# control_board.net
KiCad netlist of a schematic drawn in EAGLE
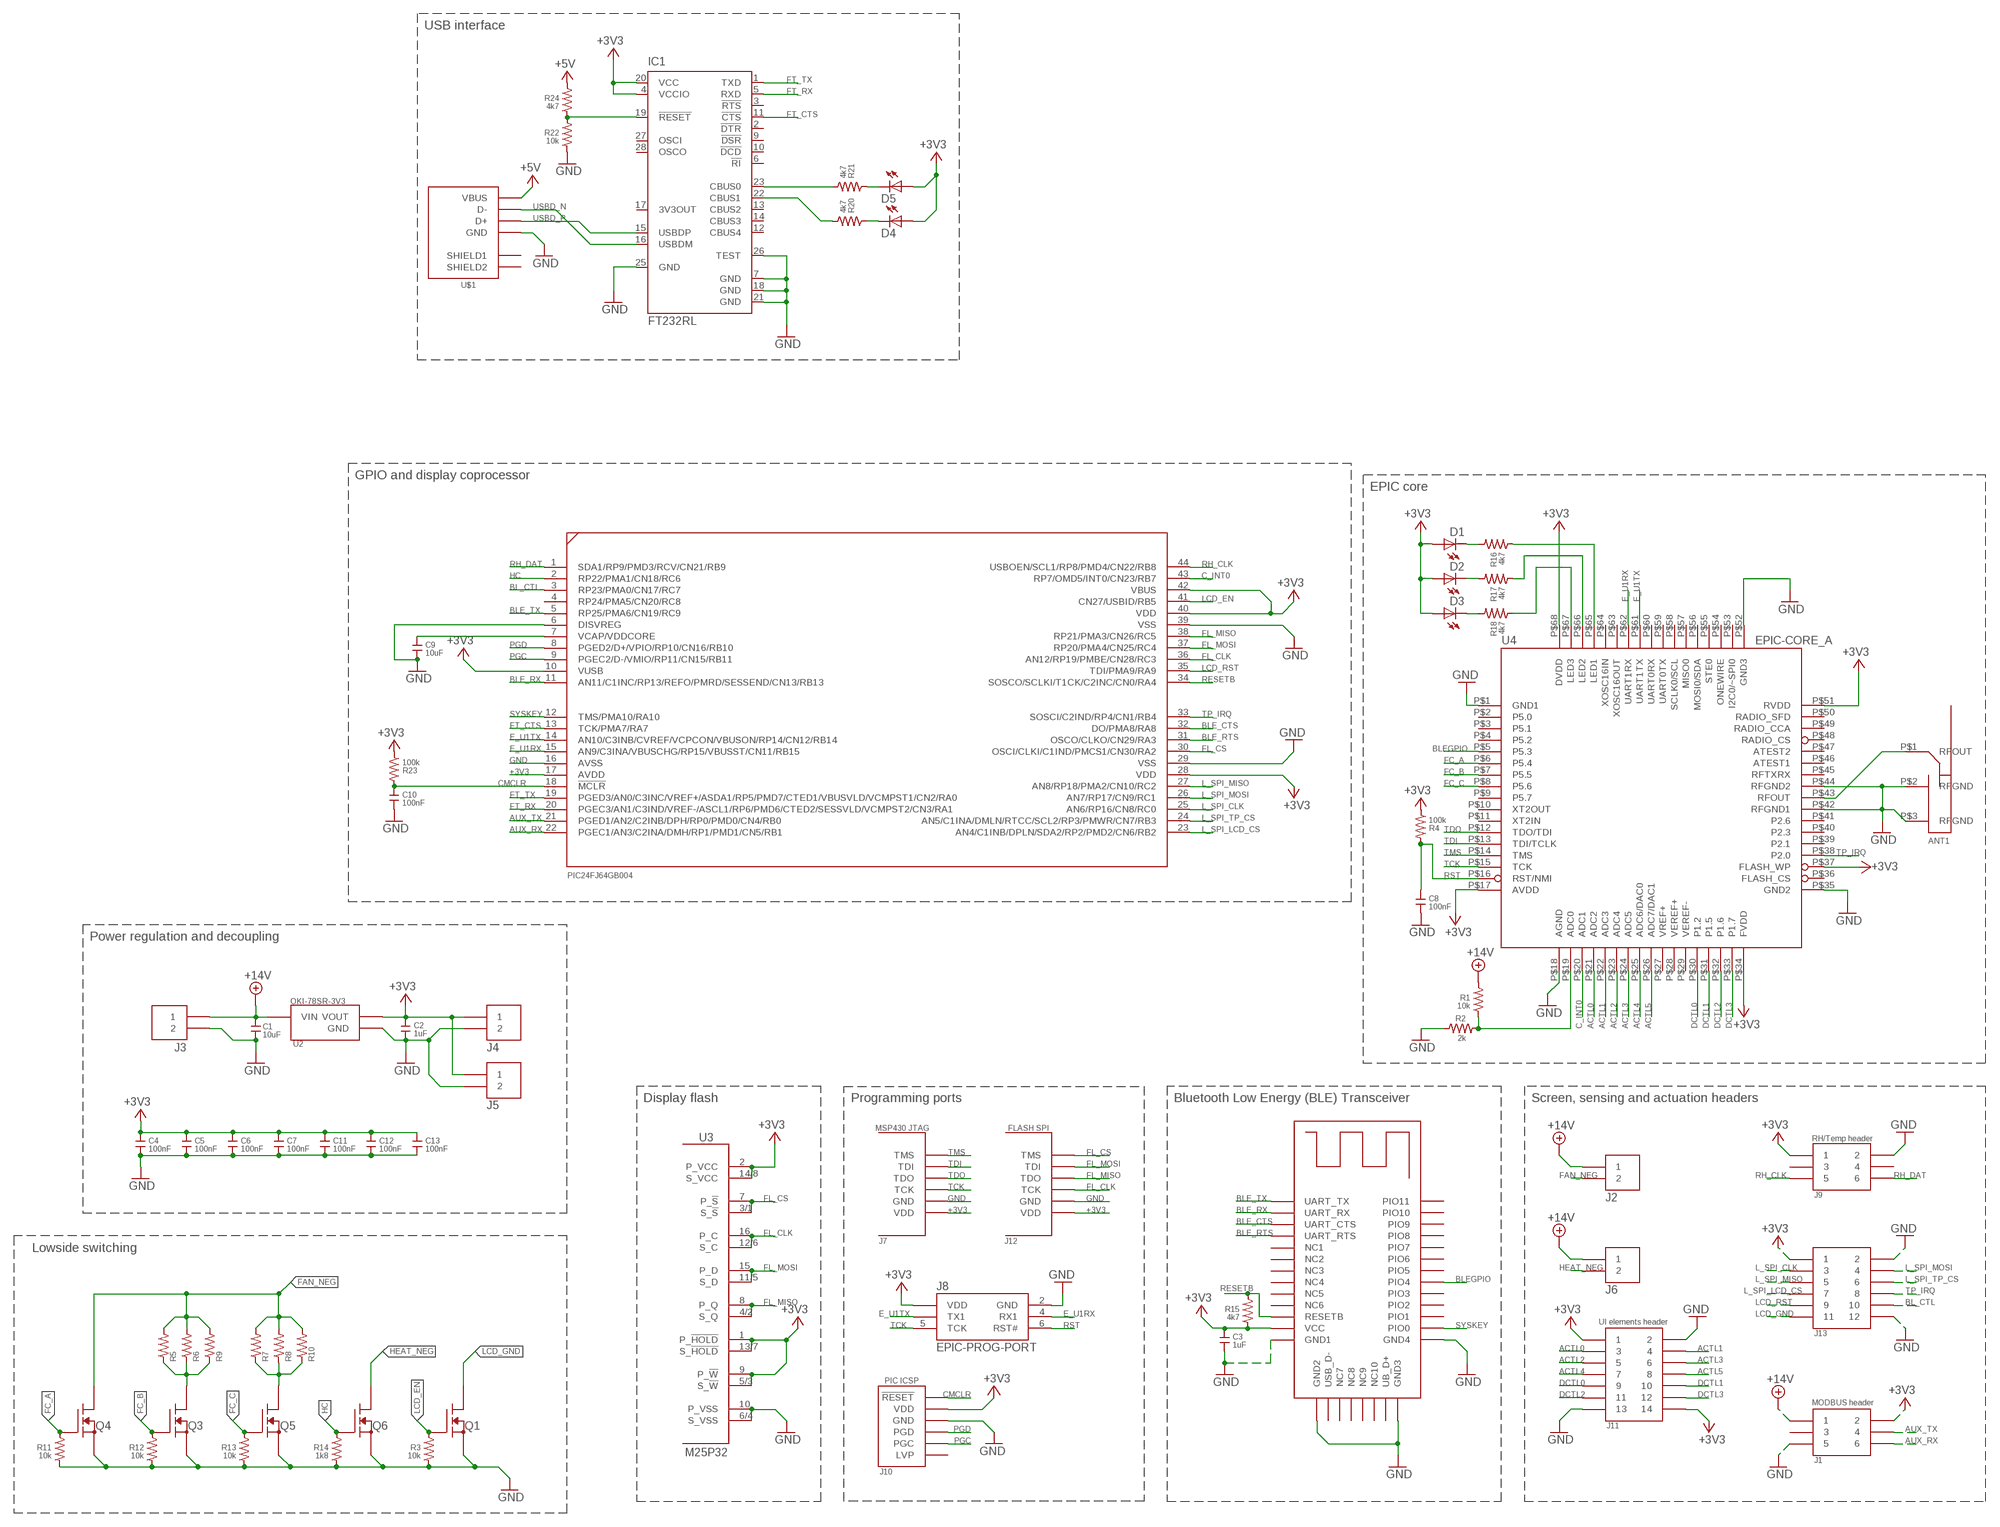
[diagram p0: schematic, sheet 1]

(export (version "E")
  (design (tool "Eeschema 10.0.6"))
  (components
    (comp (ref "ANT1")
      (value "PIFA-2.4GHZ")
      (footprint "eagle-import:PIFA-2.4GHZ")
      (libsource (lib "eagle-import") (part "PIFA-2.4GHZ"))
    )
    (comp (ref "BLE1")
      (value "HM10_BLE")
      (footprint "eagle-import:HM10")
      (libsource (lib "eagle-import") (part "HM10_BLE"))
    )
    (comp (ref "C1")
      (value "10uF")
      (footprint "eagle-import:0805")
      (libsource (lib "eagle-import") (part "0805_CAPACITOR"))
    )
    (comp (ref "C2")
      (value "1uF")
      (footprint "eagle-import:0805")
      (libsource (lib "eagle-import") (part "0805_CAPACITOR"))
    )
    (comp (ref "C3")
      (value "1uF")
      (footprint "eagle-import:0805")
      (libsource (lib "eagle-import") (part "0805_CAPACITOR"))
    )
    (comp (ref "C4")
      (value "100nF")
      (footprint "eagle-import:0805")
      (libsource (lib "eagle-import") (part "0805_CAPACITOR"))
    )
    (comp (ref "C5")
      (value "100nF")
      (footprint "eagle-import:0805")
      (libsource (lib "eagle-import") (part "0805_CAPACITOR"))
    )
    (comp (ref "C6")
      (value "100nF")
      (footprint "eagle-import:0805")
      (libsource (lib "eagle-import") (part "0805_CAPACITOR"))
    )
    (comp (ref "C7")
      (value "100nF")
      (footprint "eagle-import:0805")
      (libsource (lib "eagle-import") (part "0805_CAPACITOR"))
    )
    (comp (ref "C8")
      (value "100nF")
      (footprint "eagle-import:0805")
      (libsource (lib "eagle-import") (part "0805_CAPACITOR"))
    )
    (comp (ref "C9")
      (value "10uF")
      (footprint "eagle-import:0805")
      (libsource (lib "eagle-import") (part "0805_CAPACITOR"))
    )
    (comp (ref "C10")
      (value "100nF")
      (footprint "eagle-import:0805")
      (libsource (lib "eagle-import") (part "0805_CAPACITOR"))
    )
    (comp (ref "C11")
      (value "100nF")
      (footprint "eagle-import:0805")
      (libsource (lib "eagle-import") (part "0805_CAPACITOR"))
    )
    (comp (ref "C12")
      (value "100nF")
      (footprint "eagle-import:0805")
      (libsource (lib "eagle-import") (part "0805_CAPACITOR"))
    )
    (comp (ref "C13")
      (value "100nF")
      (footprint "eagle-import:0805")
      (libsource (lib "eagle-import") (part "0805_CAPACITOR"))
    )
    (comp (ref "D1")
      (value "LED0603")
      (footprint "eagle-import:LED-0603")
      (libsource (lib "eagle-import") (part "LED0603"))
    )
    (comp (ref "D2")
      (value "LED0603")
      (footprint "eagle-import:LED-0603")
      (libsource (lib "eagle-import") (part "LED0603"))
    )
    (comp (ref "D3")
      (value "LED0603")
      (footprint "eagle-import:LED-0603")
      (libsource (lib "eagle-import") (part "LED0603"))
    )
    (comp (ref "D4")
      (value "LED0603")
      (footprint "eagle-import:LED-0603")
      (libsource (lib "eagle-import") (part "LED0603"))
    )
    (comp (ref "D5")
      (value "LED0603")
      (footprint "eagle-import:LED-0603")
      (libsource (lib "eagle-import") (part "LED0603"))
    )
    (comp (ref "IC1")
      (value "FT232RL")
      (footprint "eagle-import:SSOP28")
      (libsource (lib "eagle-import") (part "FT232RL"))
    )
    (comp (ref "J1")
      (value "HD.1-6")
      (footprint "eagle-import:HD.1-6")
      (libsource (lib "eagle-import") (part "HD.1-6"))
    )
    (comp (ref "J2")
      (value "H.1-2")
      (footprint "eagle-import:H.1-2")
      (libsource (lib "eagle-import") (part "H.1-2"))
    )
    (comp (ref "J3")
      (value "H.1-2")
      (footprint "eagle-import:H.1-2")
      (libsource (lib "eagle-import") (part "H.1-2"))
    )
    (comp (ref "J4")
      (value "H.1-2")
      (footprint "eagle-import:H.1-2")
      (libsource (lib "eagle-import") (part "H.1-2"))
    )
    (comp (ref "J5")
      (value "H.1-2")
      (footprint "eagle-import:H.1-2")
      (libsource (lib "eagle-import") (part "H.1-2"))
    )
    (comp (ref "J6")
      (value "H.1-2")
      (footprint "eagle-import:H.1-2")
      (libsource (lib "eagle-import") (part "H.1-2"))
    )
    (comp (ref "J7")
      (value "JTAG")
      (footprint "eagle-import:JTAG")
      (libsource (lib "eagle-import") (part "JTAG"))
    )
    (comp (ref "J8")
      (value "EPIC-PROG-PORT")
      (footprint "eagle-import:HEADER2X3X2MM")
      (libsource (lib "eagle-import") (part "EPIC-PROG-PORT"))
    )
    (comp (ref "J9")
      (value "HD.1-6")
      (footprint "eagle-import:HD.1-6")
      (libsource (lib "eagle-import") (part "HD.1-6"))
    )
    (comp (ref "J10")
      (value "ICSP_HDR")
      (footprint "eagle-import:H.1-6")
      (libsource (lib "eagle-import") (part "ICSP_HDR"))
    )
    (comp (ref "J11")
      (value "HD.1-14")
      (footprint "eagle-import:HD.1-16")
      (libsource (lib "eagle-import") (part "HD.1-14"))
    )
    (comp (ref "J12")
      (value "JTAG")
      (footprint "eagle-import:JTAG")
      (libsource (lib "eagle-import") (part "JTAG"))
    )
    (comp (ref "J13")
      (value "HD.1-12")
      (footprint "eagle-import:HD.1-12")
      (libsource (lib "eagle-import") (part "HD.1-12"))
    )
    (comp (ref "Q1")
      (value "NFET_DPAK")
      (footprint "eagle-import:DPAK")
      (libsource (lib "eagle-import") (part "NFET_DPAK"))
    )
    (comp (ref "Q3")
      (value "NFET_DPAK")
      (footprint "eagle-import:DPAK")
      (libsource (lib "eagle-import") (part "NFET_DPAK"))
    )
    (comp (ref "Q4")
      (value "NFET_DPAK")
      (footprint "eagle-import:DPAK")
      (libsource (lib "eagle-import") (part "NFET_DPAK"))
    )
    (comp (ref "Q5")
      (value "NFET_DPAK")
      (footprint "eagle-import:DPAK")
      (libsource (lib "eagle-import") (part "NFET_DPAK"))
    )
    (comp (ref "Q6")
      (value "NFET_DPAK")
      (footprint "eagle-import:DPAK")
      (libsource (lib "eagle-import") (part "NFET_DPAK"))
    )
    (comp (ref "R1")
      (value "10k")
      (footprint "eagle-import:0805")
      (libsource (lib "eagle-import") (part "0805_RESISTOR"))
    )
    (comp (ref "R2")
      (value "2k")
      (footprint "eagle-import:0805")
      (libsource (lib "eagle-import") (part "0805_RESISTOR"))
    )
    (comp (ref "R3")
      (value "10k")
      (footprint "eagle-import:0805")
      (libsource (lib "eagle-import") (part "0805_RESISTOR"))
    )
    (comp (ref "R4")
      (value "100k")
      (footprint "eagle-import:0805")
      (libsource (lib "eagle-import") (part "0805_RESISTOR"))
    )
    (comp (ref "R5")
      (value "1206_RESISTOR")
      (footprint "eagle-import:1206")
      (libsource (lib "eagle-import") (part "1206_RESISTOR"))
    )
    (comp (ref "R6")
      (value "1206_RESISTOR")
      (footprint "eagle-import:1206")
      (libsource (lib "eagle-import") (part "1206_RESISTOR"))
    )
    (comp (ref "R7")
      (value "1206_RESISTOR")
      (footprint "eagle-import:1206")
      (libsource (lib "eagle-import") (part "1206_RESISTOR"))
    )
    (comp (ref "R8")
      (value "1206_RESISTOR")
      (footprint "eagle-import:1206")
      (libsource (lib "eagle-import") (part "1206_RESISTOR"))
    )
    (comp (ref "R9")
      (value "1206_RESISTOR")
      (footprint "eagle-import:1206")
      (libsource (lib "eagle-import") (part "1206_RESISTOR"))
    )
    (comp (ref "R10")
      (value "1206_RESISTOR")
      (footprint "eagle-import:1206")
      (libsource (lib "eagle-import") (part "1206_RESISTOR"))
    )
    (comp (ref "R11")
      (value "10k")
      (footprint "eagle-import:0805")
      (libsource (lib "eagle-import") (part "0805_RESISTOR"))
    )
    (comp (ref "R12")
      (value "10k")
      (footprint "eagle-import:0805")
      (libsource (lib "eagle-import") (part "0805_RESISTOR"))
    )
    (comp (ref "R13")
      (value "10k")
      (footprint "eagle-import:0805")
      (libsource (lib "eagle-import") (part "0805_RESISTOR"))
    )
    (comp (ref "R14")
      (value "1k8")
      (footprint "eagle-import:0805")
      (libsource (lib "eagle-import") (part "0805_RESISTOR"))
    )
    (comp (ref "R15")
      (value "4k7")
      (footprint "eagle-import:0805")
      (libsource (lib "eagle-import") (part "0805_RESISTOR"))
    )
    (comp (ref "R16")
      (value "4k7")
      (footprint "eagle-import:0805")
      (libsource (lib "eagle-import") (part "0805_RESISTOR"))
    )
    (comp (ref "R17")
      (value "4k7")
      (footprint "eagle-import:0805")
      (libsource (lib "eagle-import") (part "0805_RESISTOR"))
    )
    (comp (ref "R18")
      (value "4k7")
      (footprint "eagle-import:0805")
      (libsource (lib "eagle-import") (part "0805_RESISTOR"))
    )
    (comp (ref "R20")
      (value "4k7")
      (footprint "eagle-import:0805")
      (libsource (lib "eagle-import") (part "0805_RESISTOR"))
    )
    (comp (ref "R21")
      (value "4k7")
      (footprint "eagle-import:0805")
      (libsource (lib "eagle-import") (part "0805_RESISTOR"))
    )
    (comp (ref "R22")
      (value "10k")
      (footprint "eagle-import:0805")
      (libsource (lib "eagle-import") (part "0805_RESISTOR"))
    )
    (comp (ref "R23")
      (value "100k")
      (footprint "eagle-import:0805")
      (libsource (lib "eagle-import") (part "0805_RESISTOR"))
    )
    (comp (ref "R24")
      (value "4k7")
      (footprint "eagle-import:0805")
      (libsource (lib "eagle-import") (part "0805_RESISTOR"))
    )
    (comp (ref "U$1")
      (value "USB_B")
      (footprint "eagle-import:USB_MOLEX_7041")
      (libsource (lib "eagle-import") (part "USB_B"))
    )
    (comp (ref "U1")
      (value "PIC24FJ32GB004")
      (footprint "eagle-import:TQFP44")
      (libsource (lib "eagle-import") (part "PIC24FJ32GB004"))
    )
    (comp (ref "U2")
      (value "OKI-78SR_3V3_SMPS")
      (footprint "eagle-import:SMPS_MODULE")
      (libsource (lib "eagle-import") (part "OKI-78SR_3V3_SMPS"))
    )
    (comp (ref "U3")
      (value "NUMONYX_FLASH")
      (footprint "eagle-import:NUMONYX_FLASH")
      (libsource (lib "eagle-import") (part "NUMONYX_FLASH"))
    )
    (comp (ref "U4")
      (value "EPIC-CORE_A")
      (footprint "eagle-import:EPIC-LCC68")
      (libsource (lib "eagle-import") (part "EPIC-CORE_A"))
    )
  )
  (nets
    (net (code "1") (name "+3V3") (class "Default")
      (node (ref "BLE1") (pin "P$12") (pinfunction "VCC_P$12") (pintype "power_in"))
      (node (ref "C11") (pin "2") (pinfunction "P$2_2") (pintype "passive"))
      (node (ref "C12") (pin "2") (pinfunction "P$2_2") (pintype "passive"))
      (node (ref "C13") (pin "2") (pinfunction "P$2_2") (pintype "passive"))
      (node (ref "C2") (pin "2") (pinfunction "P$2_2") (pintype "passive"))
      (node (ref "C3") (pin "2") (pinfunction "P$2_2") (pintype "passive"))
      (node (ref "C4") (pin "2") (pinfunction "P$2_2") (pintype "passive"))
      (node (ref "C5") (pin "2") (pinfunction "P$2_2") (pintype "passive"))
      (node (ref "C6") (pin "2") (pinfunction "P$2_2") (pintype "passive"))
      (node (ref "C7") (pin "2") (pinfunction "P$2_2") (pintype "passive"))
      (node (ref "D1") (pin "A") (pinfunction "A_A") (pintype "passive"))
      (node (ref "D2") (pin "A") (pinfunction "A_A") (pintype "passive"))
      (node (ref "D3") (pin "A") (pinfunction "A_A") (pintype "passive"))
      (node (ref "D4") (pin "A") (pinfunction "A_A") (pintype "passive"))
      (node (ref "D5") (pin "A") (pinfunction "A_A") (pintype "passive"))
      (node (ref "IC1") (pin "20") (pinfunction "VCC_20") (pintype "power_in"))
      (node (ref "IC1") (pin "4") (pinfunction "VCCIO_4") (pintype "power_in"))
      (node (ref "J1") (pin "P2") (pinfunction "2_P2") (pintype "bidirectional"))
      (node (ref "J10") (pin "P2") (pinfunction "VDD_P2") (pintype "bidirectional"))
      (node (ref "J11") (pin "P1") (pinfunction "1_P1") (pintype "bidirectional"))
      (node (ref "J11") (pin "P14") (pinfunction "14_P14") (pintype "bidirectional"))
      (node (ref "J12") (pin "VDD") (pinfunction "VDD_VDD") (pintype "bidirectional"))
      (node (ref "J13") (pin "P1") (pinfunction "1_P1") (pintype "bidirectional"))
      (node (ref "J4") (pin "P1") (pinfunction "1_P1") (pintype "bidirectional"))
      (node (ref "J5") (pin "P1") (pinfunction "1_P1") (pintype "bidirectional"))
      (node (ref "J7") (pin "VDD") (pinfunction "VDD_VDD") (pintype "bidirectional"))
      (node (ref "J8") (pin "1") (pinfunction "VDD_1") (pintype "bidirectional"))
      (node (ref "J9") (pin "P1") (pinfunction "1_P1") (pintype "bidirectional"))
      (node (ref "R15") (pin "1") (pinfunction "P$1_1") (pintype "passive"))
      (node (ref "R23") (pin "1") (pinfunction "P$1_1") (pintype "passive"))
      (node (ref "R4") (pin "1") (pinfunction "P$1_1") (pintype "passive"))
      (node (ref "U1") (pin "10") (pinfunction "VUSB_10") (pintype "bidirectional"))
      (node (ref "U1") (pin "17") (pinfunction "AVDD_17") (pintype "bidirectional"))
      (node (ref "U1") (pin "28") (pinfunction "VDD_28") (pintype "bidirectional"))
      (node (ref "U1") (pin "40") (pinfunction "VDD_40") (pintype "bidirectional"))
      (node (ref "U1") (pin "42") (pinfunction "VBUS_42") (pintype "bidirectional"))
      (node (ref "U2") (pin "VOUT") (pinfunction "VOUT_VOUT") (pintype "power_in"))
      (node (ref "U3") (pin "1") (pinfunction "P_~{HOLD}_1") (pintype "bidirectional"))
      (node (ref "U3") (pin "13/7") (pinfunction "S_~{HOLD}_13/7") (pintype "bidirectional"))
      (node (ref "U3") (pin "14/8") (pinfunction "S_VCC_14/8") (pintype "power_in"))
      (node (ref "U3") (pin "2") (pinfunction "P_VCC_2") (pintype "power_in"))
      (node (ref "U3") (pin "5/3") (pinfunction "S_~{W}_5/3") (pintype "bidirectional"))
      (node (ref "U3") (pin "9") (pinfunction "P_~{W}_9") (pintype "bidirectional"))
      (node (ref "U4") (pin "P$17") (pinfunction "AVDD_P$17") (pintype "bidirectional"))
      (node (ref "U4") (pin "P$34") (pinfunction "FVDD_P$34") (pintype "bidirectional"))
      (node (ref "U4") (pin "P$37") (pinfunction "FLASH_WP_P$37") (pintype "bidirectional"))
      (node (ref "U4") (pin "P$51") (pinfunction "RVDD_P$51") (pintype "bidirectional"))
      (node (ref "U4") (pin "P$68") (pinfunction "DVDD_P$68") (pintype "bidirectional"))
    )
    (net (code "2") (name "+5V") (class "Default")
      (node (ref "R24") (pin "2") (pinfunction "P$2_2") (pintype "passive"))
      (node (ref "U$1") (pin "1_VBUS") (pinfunction "VBUS_1_VBUS") (pintype "bidirectional"))
    )
    (net (code "3") (name "+14V") (class "Default")
      (node (ref "C1") (pin "2") (pinfunction "P$2_2") (pintype "passive"))
      (node (ref "J1") (pin "P1") (pinfunction "1_P1") (pintype "bidirectional"))
      (node (ref "J2") (pin "P1") (pinfunction "1_P1") (pintype "bidirectional"))
      (node (ref "J3") (pin "P1") (pinfunction "1_P1") (pintype "bidirectional"))
      (node (ref "J6") (pin "P1") (pinfunction "1_P1") (pintype "bidirectional"))
      (node (ref "R1") (pin "2") (pinfunction "P$2_2") (pintype "passive"))
      (node (ref "U2") (pin "VIN") (pinfunction "VIN_VIN") (pintype "power_in"))
    )
    (net (code "4") (name "/ACTL0") (class "Default")
      (node (ref "J11") (pin "P3") (pinfunction "3_P3") (pintype "bidirectional"))
      (node (ref "U4") (pin "P$21") (pinfunction "ADC2_P$21") (pintype "bidirectional"))
    )
    (net (code "5") (name "/ACTL1") (class "Default")
      (node (ref "J11") (pin "P4") (pinfunction "4_P4") (pintype "bidirectional"))
      (node (ref "U4") (pin "P$22") (pinfunction "ADC3_P$22") (pintype "bidirectional"))
    )
    (net (code "6") (name "/ACTL2") (class "Default")
      (node (ref "J11") (pin "P5") (pinfunction "5_P5") (pintype "bidirectional"))
      (node (ref "U4") (pin "P$23") (pinfunction "ADC4_P$23") (pintype "bidirectional"))
    )
    (net (code "7") (name "/ACTL3") (class "Default")
      (node (ref "J11") (pin "P6") (pinfunction "6_P6") (pintype "bidirectional"))
      (node (ref "U4") (pin "P$24") (pinfunction "ADC5_P$24") (pintype "bidirectional"))
    )
    (net (code "8") (name "/ACTL4") (class "Default")
      (node (ref "J11") (pin "P7") (pinfunction "7_P7") (pintype "bidirectional"))
      (node (ref "U4") (pin "P$25") (pinfunction "ADC6/DAC0_P$25") (pintype "bidirectional"))
    )
    (net (code "9") (name "/ACTL5") (class "Default")
      (node (ref "J11") (pin "P8") (pinfunction "8_P8") (pintype "bidirectional"))
      (node (ref "U4") (pin "P$26") (pinfunction "ADC7/DAC1_P$26") (pintype "bidirectional"))
    )
    (net (code "10") (name "/AUX_RX") (class "Default")
      (node (ref "J1") (pin "P6") (pinfunction "6_P6") (pintype "bidirectional"))
      (node (ref "U1") (pin "22") (pinfunction "PGEC1/AN3/C2INA/DMH/RP1/PMD1/CN5/RB1_22") (pintype "bidirectional"))
    )
    (net (code "11") (name "/AUX_TX") (class "Default")
      (node (ref "J1") (pin "P4") (pinfunction "4_P4") (pintype "bidirectional"))
      (node (ref "U1") (pin "21") (pinfunction "PGED1/AN2/C2INB/DPH/RP0/PMD0/CN4/RB0_21") (pintype "bidirectional"))
    )
    (net (code "12") (name "/BLEGPIO") (class "Default")
      (node (ref "BLE1") (pin "P$27") (pinfunction "PIO4_P$27") (pintype "bidirectional"))
      (node (ref "U4") (pin "P$5") (pinfunction "P5.3_P$5") (pintype "bidirectional"))
    )
    (net (code "13") (name "/BLE_CTS") (class "Default")
      (node (ref "BLE1") (pin "P$3") (pinfunction "UART_CTS_P$3") (pintype "bidirectional"))
      (node (ref "U1") (pin "32") (pinfunction "DO/PMA8/RA8_32") (pintype "bidirectional"))
    )
    (net (code "14") (name "/BLE_RTS") (class "Default")
      (node (ref "BLE1") (pin "P$4") (pinfunction "UART_RTS_P$4") (pintype "bidirectional"))
      (node (ref "U1") (pin "31") (pinfunction "OSCO/CLKO/CN29/RA3_31") (pintype "bidirectional"))
    )
    (net (code "15") (name "/BLE_RX") (class "Default")
      (node (ref "BLE1") (pin "P$2") (pinfunction "UART_RX_P$2") (pintype "bidirectional"))
      (node (ref "U1") (pin "11") (pinfunction "AN11/C1INC/RP13/REFO/PMRD/SESSEND/CN13/RB13_11") (pintype "bidirectional"))
    )
    (net (code "16") (name "/BLE_TX") (class "Default")
      (node (ref "BLE1") (pin "P$1") (pinfunction "UART_TX_P$1") (pintype "bidirectional"))
      (node (ref "U1") (pin "5") (pinfunction "RP25/PMA6/CN19/RC9_5") (pintype "bidirectional"))
    )
    (net (code "17") (name "/BL_CTL") (class "Default")
      (node (ref "J13") (pin "P10") (pinfunction "10_P10") (pintype "bidirectional"))
      (node (ref "U1") (pin "3") (pinfunction "RP23/PMA0/CN17/RC7_3") (pintype "bidirectional"))
    )
    (net (code "18") (name "/CMCLR") (class "Default")
      (node (ref "C10") (pin "2") (pinfunction "P$2_2") (pintype "passive"))
      (node (ref "J10") (pin "P1") (pinfunction "~{RESET}_P1") (pintype "bidirectional"))
      (node (ref "R23") (pin "2") (pinfunction "P$2_2") (pintype "passive"))
      (node (ref "U1") (pin "18") (pinfunction "~{MCLR}_18") (pintype "bidirectional"))
    )
    (net (code "19") (name "/C_INT0") (class "Default")
      (node (ref "U1") (pin "43") (pinfunction "RP7/OMD5/INT0/CN23/RB7_43") (pintype "bidirectional"))
      (node (ref "U4") (pin "P$20") (pinfunction "ADC1_P$20") (pintype "bidirectional"))
    )
    (net (code "20") (name "/DCTL0") (class "Default")
      (node (ref "J11") (pin "P9") (pinfunction "9_P9") (pintype "bidirectional"))
      (node (ref "U4") (pin "P$30") (pinfunction "P1.2_P$30") (pintype "bidirectional"))
    )
    (net (code "21") (name "/DCTL1") (class "Default")
      (node (ref "J11") (pin "P10") (pinfunction "10_P10") (pintype "bidirectional"))
      (node (ref "U4") (pin "P$31") (pinfunction "P1.5_P$31") (pintype "bidirectional"))
    )
    (net (code "22") (name "/DCTL2") (class "Default")
      (node (ref "J11") (pin "P11") (pinfunction "11_P11") (pintype "bidirectional"))
      (node (ref "U4") (pin "P$32") (pinfunction "P1.6_P$32") (pintype "bidirectional"))
    )
    (net (code "23") (name "/DCTL3") (class "Default")
      (node (ref "J11") (pin "P12") (pinfunction "12_P12") (pintype "bidirectional"))
      (node (ref "U4") (pin "P$33") (pinfunction "P1.7_P$33") (pintype "bidirectional"))
    )
    (net (code "24") (name "/E_U1RX") (class "Default")
      (node (ref "J8") (pin "4") (pinfunction "RX1_4") (pintype "bidirectional"))
      (node (ref "U1") (pin "15") (pinfunction "AN9/C3INA/VBUSCHG/RP15/VBUSST/CN11/RB15_15") (pintype "bidirectional"))
      (node (ref "U4") (pin "P$62") (pinfunction "UART1RX_P$62") (pintype "bidirectional"))
    )
    (net (code "25") (name "/E_U1TX") (class "Default")
      (node (ref "J8") (pin "3") (pinfunction "TX1_3") (pintype "bidirectional"))
      (node (ref "U1") (pin "14") (pinfunction "AN10/C3INB/CVREF/VCPCON/VBUSON/RP14/CN12/RB14_14") (pintype "bidirectional"))
      (node (ref "U4") (pin "P$61") (pinfunction "UART1TX_P$61") (pintype "bidirectional"))
    )
    (net (code "26") (name "/FL_CLK") (class "Default")
      (node (ref "J12") (pin "TCK") (pinfunction "TCK_TCK") (pintype "bidirectional"))
      (node (ref "U1") (pin "36") (pinfunction "AN12/RP19/PMBE/CN28/RC3_36") (pintype "bidirectional"))
      (node (ref "U3") (pin "12/6") (pinfunction "S_C_12/6") (pintype "bidirectional"))
      (node (ref "U3") (pin "16") (pinfunction "P_C_16") (pintype "bidirectional"))
    )
    (net (code "27") (name "/FL_CS") (class "Default")
      (node (ref "J12") (pin "TMS") (pinfunction "TMS_TMS") (pintype "bidirectional"))
      (node (ref "U1") (pin "30") (pinfunction "OSCI/CLKI/C1IND/PMCS1/CN30/RA2_30") (pintype "bidirectional"))
      (node (ref "U3") (pin "3/1") (pinfunction "S_~{S}_3/1") (pintype "bidirectional"))
      (node (ref "U3") (pin "7") (pinfunction "P_~{S}_7") (pintype "bidirectional"))
    )
    (net (code "28") (name "/FL_MISO") (class "Default")
      (node (ref "J12") (pin "TDO") (pinfunction "TDO_TDO") (pintype "bidirectional"))
      (node (ref "U1") (pin "38") (pinfunction "RP21/PMA3/CN26/RC5_38") (pintype "bidirectional"))
      (node (ref "U3") (pin "4/2") (pinfunction "S_Q_4/2") (pintype "bidirectional"))
      (node (ref "U3") (pin "8") (pinfunction "P_Q_8") (pintype "bidirectional"))
    )
    (net (code "29") (name "/FL_MOSI") (class "Default")
      (node (ref "J12") (pin "TDI") (pinfunction "TDI_TDI") (pintype "bidirectional"))
      (node (ref "U1") (pin "37") (pinfunction "RP20/PMA4/CN25/RC4_37") (pintype "bidirectional"))
      (node (ref "U3") (pin "11/5") (pinfunction "S_D_11/5") (pintype "bidirectional"))
      (node (ref "U3") (pin "15") (pinfunction "P_D_15") (pintype "bidirectional"))
    )
    (net (code "30") (name "/FT_CTS") (class "Default")
      (node (ref "IC1") (pin "11") (pinfunction "~{CTS}_11") (pintype "input"))
      (node (ref "U1") (pin "13") (pinfunction "TCK/PMA7/RA7_13") (pintype "bidirectional"))
    )
    (net (code "31") (name "/FT_RX") (class "Default")
      (node (ref "IC1") (pin "5") (pinfunction "RXD_5") (pintype "input"))
      (node (ref "U1") (pin "20") (pinfunction "PGEC3/AN1/C3IND/VREF-/ASCL1/RP6/PMD6/CTED2/SESSVLD/VCMPST2/CN3/RA1_20") (pintype "bidirectional"))
    )
    (net (code "32") (name "/FT_TX") (class "Default")
      (node (ref "IC1") (pin "1") (pinfunction "TXD_1") (pintype "output"))
      (node (ref "U1") (pin "19") (pinfunction "PGED3/AN0/C3INC/VREF+/ASDA1/RP5/PMD7/CTED1/VBUSVLD/VCMPST1/CN2/RA0_19") (pintype "bidirectional"))
    )
    (net (code "33") (name "/LCD_RST") (class "Default")
      (node (ref "J13") (pin "P9") (pinfunction "9_P9") (pintype "bidirectional"))
      (node (ref "U1") (pin "35") (pinfunction "TDI/PMA9/RA9_35") (pintype "bidirectional"))
    )
    (net (code "34") (name "/L_SPI_CLK") (class "Default")
      (node (ref "J13") (pin "P3") (pinfunction "3_P3") (pintype "bidirectional"))
      (node (ref "U1") (pin "25") (pinfunction "AN6/RP16/CN8/RC0_25") (pintype "bidirectional"))
    )
    (net (code "35") (name "/L_SPI_LCD_CS") (class "Default")
      (node (ref "J13") (pin "P7") (pinfunction "7_P7") (pintype "bidirectional"))
      (node (ref "U1") (pin "23") (pinfunction "AN4/C1INB/DPLN/SDA2/RP2/PMD2/CN6/RB2_23") (pintype "bidirectional"))
    )
    (net (code "36") (name "/L_SPI_MISO") (class "Default")
      (node (ref "J13") (pin "P5") (pinfunction "5_P5") (pintype "bidirectional"))
      (node (ref "U1") (pin "27") (pinfunction "AN8/RP18/PMA2/CN10/RC2_27") (pintype "bidirectional"))
    )
    (net (code "37") (name "/L_SPI_MOSI") (class "Default")
      (node (ref "J13") (pin "P4") (pinfunction "4_P4") (pintype "bidirectional"))
      (node (ref "U1") (pin "26") (pinfunction "AN7/RP17/CN9/RC1_26") (pintype "bidirectional"))
    )
    (net (code "38") (name "/L_SPI_TP_CS") (class "Default")
      (node (ref "J13") (pin "P6") (pinfunction "6_P6") (pintype "bidirectional"))
      (node (ref "U1") (pin "24") (pinfunction "AN5/C1INA/DMLN/RTCC/SCL2/RP3/PMWR/CN7/RB3_24") (pintype "bidirectional"))
    )
    (net (code "39") (name "/PGC") (class "Default")
      (node (ref "J10") (pin "P5") (pinfunction "PGC_P5") (pintype "bidirectional"))
      (node (ref "U1") (pin "9") (pinfunction "PGEC2/D-/VMIO/RP11/CN15/RB11_9") (pintype "bidirectional"))
    )
    (net (code "40") (name "/PGD") (class "Default")
      (node (ref "J10") (pin "P4") (pinfunction "PGD_P4") (pintype "bidirectional"))
      (node (ref "U1") (pin "8") (pinfunction "PGED2/D+/VPIO/RP10/CN16/RB10_8") (pintype "bidirectional"))
    )
    (net (code "41") (name "/RESETB") (class "Default")
      (node (ref "BLE1") (pin "P$11") (pinfunction "RESETB_P$11") (pintype "input"))
      (node (ref "R15") (pin "2") (pinfunction "P$2_2") (pintype "passive"))
      (node (ref "U1") (pin "34") (pinfunction "SOSCO/SCLKI/T1CK/C2INC/CN0/RA4_34") (pintype "bidirectional"))
    )
    (net (code "42") (name "/RH_CLK") (class "Default")
      (node (ref "J9") (pin "P5") (pinfunction "5_P5") (pintype "bidirectional"))
      (node (ref "U1") (pin "44") (pinfunction "USBOEN/SCL1/RP8/PMD4/CN22/RB8_44") (pintype "bidirectional"))
    )
    (net (code "43") (name "/RH_DAT") (class "Default")
      (node (ref "J9") (pin "P6") (pinfunction "6_P6") (pintype "bidirectional"))
      (node (ref "U1") (pin "1") (pinfunction "SDA1/RP9/PMD3/RCV/CN21/RB9_1") (pintype "bidirectional"))
    )
    (net (code "44") (name "/RST") (class "Default")
      (node (ref "C8") (pin "2") (pinfunction "P$2_2") (pintype "passive"))
      (node (ref "J8") (pin "6") (pinfunction "RST#_6") (pintype "bidirectional"))
      (node (ref "R4") (pin "2") (pinfunction "P$2_2") (pintype "passive"))
      (node (ref "U4") (pin "P$16") (pinfunction "RST/NMI_P$16") (pintype "bidirectional"))
    )
    (net (code "45") (name "/SYSKEY") (class "Default")
      (node (ref "BLE1") (pin "P$23") (pinfunction "PIO0_P$23") (pintype "bidirectional"))
      (node (ref "U1") (pin "12") (pinfunction "TMS/PMA10/RA10_12") (pintype "bidirectional"))
    )
    (net (code "46") (name "/TCK") (class "Default")
      (node (ref "J7") (pin "TCK") (pinfunction "TCK_TCK") (pintype "bidirectional"))
      (node (ref "J8") (pin "5") (pinfunction "TCK_5") (pintype "bidirectional"))
      (node (ref "U4") (pin "P$15") (pinfunction "TCK_P$15") (pintype "bidirectional"))
    )
    (net (code "47") (name "/TDI") (class "Default")
      (node (ref "J7") (pin "TDI") (pinfunction "TDI_TDI") (pintype "bidirectional"))
      (node (ref "U4") (pin "P$13") (pinfunction "TDI/TCLK_P$13") (pintype "bidirectional"))
    )
    (net (code "48") (name "/TDO") (class "Default")
      (node (ref "J7") (pin "TDO") (pinfunction "TDO_TDO") (pintype "bidirectional"))
      (node (ref "U4") (pin "P$12") (pinfunction "TDO/TDI_P$12") (pintype "bidirectional"))
    )
    (net (code "49") (name "/TMS") (class "Default")
      (node (ref "J7") (pin "TMS") (pinfunction "TMS_TMS") (pintype "bidirectional"))
      (node (ref "U4") (pin "P$14") (pinfunction "TMS_P$14") (pintype "bidirectional"))
    )
    (net (code "50") (name "/TP_IRQ") (class "Default")
      (node (ref "J13") (pin "P8") (pinfunction "8_P8") (pintype "bidirectional"))
      (node (ref "U1") (pin "33") (pinfunction "SOSCI/C2IND/RP4/CN1/RB4_33") (pintype "bidirectional"))
      (node (ref "U4") (pin "P$38") (pinfunction "P2.0_P$38") (pintype "bidirectional"))
    )
    (net (code "51") (name "/USBD_N") (class "Default")
      (node (ref "IC1") (pin "16") (pinfunction "USBDM_16") (pintype "bidirectional"))
      (node (ref "U$1") (pin "2_D-") (pinfunction "D-_2_D-") (pintype "bidirectional"))
    )
    (net (code "52") (name "/USBD_P") (class "Default")
      (node (ref "IC1") (pin "15") (pinfunction "USBDP_15") (pintype "bidirectional"))
      (node (ref "U$1") (pin "3_D+") (pinfunction "D+_3_D+") (pintype "bidirectional"))
    )
    (net (code "53") (name "FAN_NEG") (class "Default")
      (node (ref "J2") (pin "P2") (pinfunction "2_P2") (pintype "bidirectional"))
      (node (ref "Q4") (pin "TAG") (pinfunction "D_TAG") (pintype "passive"))
      (node (ref "R10") (pin "2") (pinfunction "P$2_2") (pintype "passive"))
      (node (ref "R5") (pin "2") (pinfunction "P$2_2") (pintype "passive"))
      (node (ref "R6") (pin "2") (pinfunction "P$2_2") (pintype "passive"))
      (node (ref "R7") (pin "2") (pinfunction "P$2_2") (pintype "passive"))
      (node (ref "R8") (pin "2") (pinfunction "P$2_2") (pintype "passive"))
      (node (ref "R9") (pin "2") (pinfunction "P$2_2") (pintype "passive"))
    )
    (net (code "54") (name "FC_A") (class "Default")
      (node (ref "Q4") (pin "P1") (pinfunction "G_P1") (pintype "passive"))
      (node (ref "R11") (pin "2") (pinfunction "P$2_2") (pintype "passive"))
      (node (ref "U4") (pin "P$6") (pinfunction "P5.4_P$6") (pintype "bidirectional"))
    )
    (net (code "55") (name "FC_B") (class "Default")
      (node (ref "Q3") (pin "P1") (pinfunction "G_P1") (pintype "passive"))
      (node (ref "R12") (pin "2") (pinfunction "P$2_2") (pintype "passive"))
      (node (ref "U4") (pin "P$7") (pinfunction "P5.5_P$7") (pintype "bidirectional"))
    )
    (net (code "56") (name "FC_C") (class "Default")
      (node (ref "Q5") (pin "P1") (pinfunction "G_P1") (pintype "passive"))
      (node (ref "R13") (pin "2") (pinfunction "P$2_2") (pintype "passive"))
      (node (ref "U4") (pin "P$8") (pinfunction "P5.6_P$8") (pintype "bidirectional"))
    )
    (net (code "57") (name "GND") (class "Default")
      (node (ref "ANT1") (pin "P$2") (pinfunction "RFGND_P$2") (pintype "bidirectional"))
      (node (ref "ANT1") (pin "P$3") (pinfunction "RFGND_P$3") (pintype "bidirectional"))
      (node (ref "BLE1") (pin "P$13") (pinfunction "GND1_P$13") (pintype "power_in"))
      (node (ref "BLE1") (pin "P$14") (pinfunction "GND2_P$14") (pintype "power_in"))
      (node (ref "BLE1") (pin "P$21") (pinfunction "GND3_P$21") (pintype "power_in"))
      (node (ref "BLE1") (pin "P$22") (pinfunction "GND4_P$22") (pintype "power_in"))
      (node (ref "C1") (pin "1") (pinfunction "P$1_1") (pintype "passive"))
      (node (ref "C10") (pin "1") (pinfunction "P$1_1") (pintype "passive"))
      (node (ref "C11") (pin "1") (pinfunction "P$1_1") (pintype "passive"))
      (node (ref "C12") (pin "1") (pinfunction "P$1_1") (pintype "passive"))
      (node (ref "C13") (pin "1") (pinfunction "P$1_1") (pintype "passive"))
      (node (ref "C2") (pin "1") (pinfunction "P$1_1") (pintype "passive"))
      (node (ref "C3") (pin "1") (pinfunction "P$1_1") (pintype "passive"))
      (node (ref "C4") (pin "1") (pinfunction "P$1_1") (pintype "passive"))
      (node (ref "C5") (pin "1") (pinfunction "P$1_1") (pintype "passive"))
      (node (ref "C6") (pin "1") (pinfunction "P$1_1") (pintype "passive"))
      (node (ref "C7") (pin "1") (pinfunction "P$1_1") (pintype "passive"))
      (node (ref "C8") (pin "1") (pinfunction "P$1_1") (pintype "passive"))
      (node (ref "C9") (pin "1") (pinfunction "P$1_1") (pintype "passive"))
      (node (ref "IC1") (pin "18") (pinfunction "GND_18") (pintype "power_in"))
      (node (ref "IC1") (pin "21") (pinfunction "GND_21") (pintype "power_in"))
      (node (ref "IC1") (pin "25") (pinfunction "GND_25") (pintype "power_in"))
      (node (ref "IC1") (pin "26") (pinfunction "TEST_26") (pintype "input"))
      (node (ref "IC1") (pin "7") (pinfunction "GND_7") (pintype "power_in"))
      (node (ref "J1") (pin "P5") (pinfunction "5_P5") (pintype "bidirectional"))
      (node (ref "J10") (pin "P3") (pinfunction "GND_P3") (pintype "bidirectional"))
      (node (ref "J11") (pin "P13") (pinfunction "13_P13") (pintype "bidirectional"))
      (node (ref "J11") (pin "P2") (pinfunction "2_P2") (pintype "bidirectional"))
      (node (ref "J12") (pin "GND") (pinfunction "GND_GND") (pintype "bidirectional"))
      (node (ref "J13") (pin "P12") (pinfunction "12_P12") (pintype "bidirectional"))
      (node (ref "J13") (pin "P2") (pinfunction "2_P2") (pintype "bidirectional"))
      (node (ref "J3") (pin "P2") (pinfunction "2_P2") (pintype "bidirectional"))
      (node (ref "J4") (pin "P2") (pinfunction "2_P2") (pintype "bidirectional"))
      (node (ref "J5") (pin "P2") (pinfunction "2_P2") (pintype "bidirectional"))
      (node (ref "J7") (pin "GND") (pinfunction "GND_GND") (pintype "bidirectional"))
      (node (ref "J8") (pin "2") (pinfunction "GND_2") (pintype "bidirectional"))
      (node (ref "J9") (pin "P2") (pinfunction "2_P2") (pintype "bidirectional"))
      (node (ref "Q1") (pin "P3") (pinfunction "S_P3") (pintype "passive"))
      (node (ref "Q3") (pin "P3") (pinfunction "S_P3") (pintype "passive"))
      (node (ref "Q4") (pin "P3") (pinfunction "S_P3") (pintype "passive"))
      (node (ref "Q5") (pin "P3") (pinfunction "S_P3") (pintype "passive"))
      (node (ref "Q6") (pin "P3") (pinfunction "S_P3") (pintype "passive"))
      (node (ref "R11") (pin "1") (pinfunction "P$1_1") (pintype "passive"))
      (node (ref "R12") (pin "1") (pinfunction "P$1_1") (pintype "passive"))
      (node (ref "R13") (pin "1") (pinfunction "P$1_1") (pintype "passive"))
      (node (ref "R14") (pin "1") (pinfunction "P$1_1") (pintype "passive"))
      (node (ref "R2") (pin "1") (pinfunction "P$1_1") (pintype "passive"))
      (node (ref "R22") (pin "1") (pinfunction "P$1_1") (pintype "passive"))
      (node (ref "R3") (pin "1") (pinfunction "P$1_1") (pintype "passive"))
      (node (ref "U$1") (pin "4_GND") (pinfunction "GND_4_GND") (pintype "bidirectional"))
      (node (ref "U1") (pin "16") (pinfunction "AVSS_16") (pintype "bidirectional"))
      (node (ref "U1") (pin "29") (pinfunction "VSS_29") (pintype "bidirectional"))
      (node (ref "U1") (pin "39") (pinfunction "VSS_39") (pintype "bidirectional"))
      (node (ref "U1") (pin "6") (pinfunction "DISVREG_6") (pintype "bidirectional"))
      (node (ref "U2") (pin "GND") (pinfunction "GND_GND") (pintype "power_in"))
      (node (ref "U3") (pin "10") (pinfunction "P_VSS_10") (pintype "power_in"))
      (node (ref "U3") (pin "6/4") (pinfunction "S_VSS_6/4") (pintype "power_in"))
      (node (ref "U4") (pin "P$1") (pinfunction "GND1_P$1") (pintype "bidirectional"))
      (node (ref "U4") (pin "P$18") (pinfunction "AGND_P$18") (pintype "bidirectional"))
      (node (ref "U4") (pin "P$35") (pinfunction "GND2_P$35") (pintype "bidirectional"))
      (node (ref "U4") (pin "P$42") (pinfunction "RFGND1_P$42") (pintype "bidirectional"))
      (node (ref "U4") (pin "P$44") (pinfunction "RFGND2_P$44") (pintype "bidirectional"))
      (node (ref "U4") (pin "P$52") (pinfunction "GND3_P$52") (pintype "bidirectional"))
    )
    (net (code "58") (name "HC") (class "Default")
      (node (ref "Q6") (pin "P1") (pinfunction "G_P1") (pintype "passive"))
      (node (ref "R14") (pin "2") (pinfunction "P$2_2") (pintype "passive"))
      (node (ref "U1") (pin "2") (pinfunction "RP22/PMA1/CN18/RC6_2") (pintype "bidirectional"))
    )
    (net (code "59") (name "HEAT_NEG") (class "Default")
      (node (ref "J6") (pin "P2") (pinfunction "2_P2") (pintype "bidirectional"))
      (node (ref "Q6") (pin "TAG") (pinfunction "D_TAG") (pintype "passive"))
    )
    (net (code "60") (name "LCD_EN") (class "Default")
      (node (ref "Q1") (pin "P1") (pinfunction "G_P1") (pintype "passive"))
      (node (ref "R3") (pin "2") (pinfunction "P$2_2") (pintype "passive"))
      (node (ref "U1") (pin "41") (pinfunction "CN27/USBID/RB5_41") (pintype "bidirectional"))
    )
    (net (code "61") (name "LCD_GND") (class "Default")
      (node (ref "J13") (pin "P11") (pinfunction "11_P11") (pintype "bidirectional"))
      (node (ref "Q1") (pin "TAG") (pinfunction "D_TAG") (pintype "passive"))
    )
    (net (code "62") (name "Net-(ANT1-RFOUT)") (class "Default")
      (node (ref "ANT1") (pin "P$1") (pinfunction "RFOUT_P$1") (pintype "bidirectional"))
      (node (ref "U4") (pin "P$43") (pinfunction "RFOUT_P$43") (pintype "bidirectional"))
    )
    (net (code "63") (name "Net-(C9-P$2)") (class "Default")
      (node (ref "C9") (pin "2") (pinfunction "P$2_2") (pintype "passive"))
      (node (ref "U1") (pin "7") (pinfunction "VCAP/VDDCORE_7") (pintype "bidirectional"))
    )
    (net (code "64") (name "Net-(IC1-CBUS0)") (class "Default")
      (node (ref "IC1") (pin "23") (pinfunction "CBUS0_23") (pintype "bidirectional"))
      (node (ref "R21") (pin "1") (pinfunction "P$1_1") (pintype "passive"))
    )
    (net (code "65") (name "Net-(IC1-CBUS1)") (class "Default")
      (node (ref "IC1") (pin "22") (pinfunction "CBUS1_22") (pintype "bidirectional"))
      (node (ref "R20") (pin "1") (pinfunction "P$1_1") (pintype "passive"))
    )
    (net (code "66") (name "Net-(IC1-~{RESET})") (class "Default")
      (node (ref "IC1") (pin "19") (pinfunction "~{RESET}_19") (pintype "input"))
      (node (ref "R22") (pin "2") (pinfunction "P$2_2") (pintype "passive"))
      (node (ref "R24") (pin "1") (pinfunction "P$1_1") (pintype "passive"))
    )
    (net (code "67") (name "Net-(Q3-D)") (class "Default")
      (node (ref "Q3") (pin "TAG") (pinfunction "D_TAG") (pintype "passive"))
      (node (ref "R5") (pin "1") (pinfunction "P$1_1") (pintype "passive"))
      (node (ref "R6") (pin "1") (pinfunction "P$1_1") (pintype "passive"))
      (node (ref "R9") (pin "1") (pinfunction "P$1_1") (pintype "passive"))
    )
    (net (code "68") (name "Net-(Q5-D)") (class "Default")
      (node (ref "Q5") (pin "TAG") (pinfunction "D_TAG") (pintype "passive"))
      (node (ref "R10") (pin "1") (pinfunction "P$1_1") (pintype "passive"))
      (node (ref "R7") (pin "1") (pinfunction "P$1_1") (pintype "passive"))
      (node (ref "R8") (pin "1") (pinfunction "P$1_1") (pintype "passive"))
    )
    (net (code "69") (name "Net-(R1-P$1)") (class "Default")
      (node (ref "R1") (pin "1") (pinfunction "P$1_1") (pintype "passive"))
      (node (ref "R2") (pin "2") (pinfunction "P$2_2") (pintype "passive"))
      (node (ref "U4") (pin "P$19") (pinfunction "ADC0_P$19") (pintype "bidirectional"))
    )
    (net (code "70") (name "Net-(R16-P$1)") (class "Default")
      (node (ref "R16") (pin "1") (pinfunction "P$1_1") (pintype "passive"))
      (node (ref "U4") (pin "P$65") (pinfunction "LED1_P$65") (pintype "bidirectional"))
    )
    (net (code "71") (name "Net-(R16-P$2)") (class "Default")
      (node (ref "D1") (pin "C") (pinfunction "C_C") (pintype "passive"))
      (node (ref "R16") (pin "2") (pinfunction "P$2_2") (pintype "passive"))
    )
    (net (code "72") (name "Net-(R17-P$1)") (class "Default")
      (node (ref "R17") (pin "1") (pinfunction "P$1_1") (pintype "passive"))
      (node (ref "U4") (pin "P$66") (pinfunction "LED2_P$66") (pintype "bidirectional"))
    )
    (net (code "73") (name "Net-(R17-P$2)") (class "Default")
      (node (ref "D2") (pin "C") (pinfunction "C_C") (pintype "passive"))
      (node (ref "R17") (pin "2") (pinfunction "P$2_2") (pintype "passive"))
    )
    (net (code "74") (name "Net-(R18-P$1)") (class "Default")
      (node (ref "R18") (pin "1") (pinfunction "P$1_1") (pintype "passive"))
      (node (ref "U4") (pin "P$67") (pinfunction "LED3_P$67") (pintype "bidirectional"))
    )
    (net (code "75") (name "Net-(R18-P$2)") (class "Default")
      (node (ref "D3") (pin "C") (pinfunction "C_C") (pintype "passive"))
      (node (ref "R18") (pin "2") (pinfunction "P$2_2") (pintype "passive"))
    )
    (net (code "76") (name "Net-(R20-P$2)") (class "Default")
      (node (ref "D4") (pin "C") (pinfunction "C_C") (pintype "passive"))
      (node (ref "R20") (pin "2") (pinfunction "P$2_2") (pintype "passive"))
    )
    (net (code "77") (name "Net-(R21-P$2)") (class "Default")
      (node (ref "D5") (pin "C") (pinfunction "C_C") (pintype "passive"))
      (node (ref "R21") (pin "2") (pinfunction "P$2_2") (pintype "passive"))
    )
    (net (code "78") (name "unconnected-(BLE1-NC1-PadP$5)") (class "Default")
      (node (ref "BLE1") (pin "P$5") (pinfunction "NC1_P$5") (pintype "no_connect"))
    )
    (net (code "79") (name "unconnected-(BLE1-NC2-PadP$6)") (class "Default")
      (node (ref "BLE1") (pin "P$6") (pinfunction "NC2_P$6") (pintype "no_connect"))
    )
    (net (code "80") (name "unconnected-(BLE1-NC3-PadP$7)") (class "Default")
      (node (ref "BLE1") (pin "P$7") (pinfunction "NC3_P$7") (pintype "no_connect"))
    )
    (net (code "81") (name "unconnected-(BLE1-NC4-PadP$8)") (class "Default")
      (node (ref "BLE1") (pin "P$8") (pinfunction "NC4_P$8") (pintype "no_connect"))
    )
    (net (code "82") (name "unconnected-(BLE1-NC5-PadP$9)") (class "Default")
      (node (ref "BLE1") (pin "P$9") (pinfunction "NC5_P$9") (pintype "no_connect"))
    )
    (net (code "83") (name "unconnected-(BLE1-NC6-PadP$10)") (class "Default")
      (node (ref "BLE1") (pin "P$10") (pinfunction "NC6_P$10") (pintype "no_connect"))
    )
    (net (code "84") (name "unconnected-(BLE1-NC7-PadP$16)") (class "Default")
      (node (ref "BLE1") (pin "P$16") (pinfunction "NC7_P$16") (pintype "no_connect"))
    )
    (net (code "85") (name "unconnected-(BLE1-NC8-PadP$17)") (class "Default")
      (node (ref "BLE1") (pin "P$17") (pinfunction "NC8_P$17") (pintype "no_connect"))
    )
    (net (code "86") (name "unconnected-(BLE1-NC9-PadP$18)") (class "Default")
      (node (ref "BLE1") (pin "P$18") (pinfunction "NC9_P$18") (pintype "no_connect"))
    )
    (net (code "87") (name "unconnected-(BLE1-NC10-PadP$19)") (class "Default")
      (node (ref "BLE1") (pin "P$19") (pinfunction "NC10_P$19") (pintype "no_connect"))
    )
    (net (code "88") (name "unconnected-(BLE1-PIO1-PadP$24)") (class "Default")
      (node (ref "BLE1") (pin "P$24") (pinfunction "PIO1_P$24") (pintype "bidirectional"))
    )
    (net (code "89") (name "unconnected-(BLE1-PIO2-PadP$25)") (class "Default")
      (node (ref "BLE1") (pin "P$25") (pinfunction "PIO2_P$25") (pintype "bidirectional"))
    )
    (net (code "90") (name "unconnected-(BLE1-PIO3-PadP$26)") (class "Default")
      (node (ref "BLE1") (pin "P$26") (pinfunction "PIO3_P$26") (pintype "bidirectional"))
    )
    (net (code "91") (name "unconnected-(BLE1-PIO5-PadP$28)") (class "Default")
      (node (ref "BLE1") (pin "P$28") (pinfunction "PIO5_P$28") (pintype "bidirectional"))
    )
    (net (code "92") (name "unconnected-(BLE1-PIO6-PadP$29)") (class "Default")
      (node (ref "BLE1") (pin "P$29") (pinfunction "PIO6_P$29") (pintype "bidirectional"))
    )
    (net (code "93") (name "unconnected-(BLE1-PIO7-PadP$30)") (class "Default")
      (node (ref "BLE1") (pin "P$30") (pinfunction "PIO7_P$30") (pintype "bidirectional"))
    )
    (net (code "94") (name "unconnected-(BLE1-PIO8-PadP$31)") (class "Default")
      (node (ref "BLE1") (pin "P$31") (pinfunction "PIO8_P$31") (pintype "bidirectional"))
    )
    (net (code "95") (name "unconnected-(BLE1-PIO9-PadP$32)") (class "Default")
      (node (ref "BLE1") (pin "P$32") (pinfunction "PIO9_P$32") (pintype "bidirectional"))
    )
    (net (code "96") (name "unconnected-(BLE1-PIO10-PadP$33)") (class "Default")
      (node (ref "BLE1") (pin "P$33") (pinfunction "PIO10_P$33") (pintype "bidirectional"))
    )
    (net (code "97") (name "unconnected-(BLE1-PIO11-PadP$34)") (class "Default")
      (node (ref "BLE1") (pin "P$34") (pinfunction "PIO11_P$34") (pintype "bidirectional"))
    )
    (net (code "98") (name "unconnected-(BLE1-UB_D+-PadP$20)") (class "Default")
      (node (ref "BLE1") (pin "P$20") (pinfunction "UB_D+_P$20") (pintype "bidirectional"))
    )
    (net (code "99") (name "unconnected-(BLE1-USB_D--PadP$15)") (class "Default")
      (node (ref "BLE1") (pin "P$15") (pinfunction "USB_D-_P$15") (pintype "bidirectional"))
    )
    (net (code "100") (name "unconnected-(IC1-3V3OUT-Pad17)") (class "Default")
      (node (ref "IC1") (pin "17") (pinfunction "3V3OUT_17") (pintype "output"))
    )
    (net (code "101") (name "unconnected-(IC1-CBUS2-Pad13)") (class "Default")
      (node (ref "IC1") (pin "13") (pinfunction "CBUS2_13") (pintype "bidirectional"))
    )
    (net (code "102") (name "unconnected-(IC1-CBUS3-Pad14)") (class "Default")
      (node (ref "IC1") (pin "14") (pinfunction "CBUS3_14") (pintype "bidirectional"))
    )
    (net (code "103") (name "unconnected-(IC1-CBUS4-Pad12)") (class "Default")
      (node (ref "IC1") (pin "12") (pinfunction "CBUS4_12") (pintype "bidirectional"))
    )
    (net (code "104") (name "unconnected-(IC1-OSCI-Pad27)") (class "Default")
      (node (ref "IC1") (pin "27") (pinfunction "OSCI_27") (pintype "input"))
    )
    (net (code "105") (name "unconnected-(IC1-OSCO-Pad28)") (class "Default")
      (node (ref "IC1") (pin "28") (pinfunction "OSCO_28") (pintype "output"))
    )
    (net (code "106") (name "unconnected-(IC1-~{DCD}-Pad10)") (class "Default")
      (node (ref "IC1") (pin "10") (pinfunction "~{DCD}_10") (pintype "input"))
    )
    (net (code "107") (name "unconnected-(IC1-~{DSR}-Pad9)") (class "Default")
      (node (ref "IC1") (pin "9") (pinfunction "~{DSR}_9") (pintype "input"))
    )
    (net (code "108") (name "unconnected-(IC1-~{DTR}-Pad2)") (class "Default")
      (node (ref "IC1") (pin "2") (pinfunction "~{DTR}_2") (pintype "output"))
    )
    (net (code "109") (name "unconnected-(IC1-~{RI}-Pad6)") (class "Default")
      (node (ref "IC1") (pin "6") (pinfunction "~{RI}_6") (pintype "input"))
    )
    (net (code "110") (name "unconnected-(IC1-~{RTS}-Pad3)") (class "Default")
      (node (ref "IC1") (pin "3") (pinfunction "~{RTS}_3") (pintype "output"))
    )
    (net (code "111") (name "unconnected-(J1-3-PadP3)") (class "Default")
      (node (ref "J1") (pin "P3") (pinfunction "3_P3") (pintype "bidirectional"))
    )
    (net (code "112") (name "unconnected-(J9-3-PadP3)") (class "Default")
      (node (ref "J9") (pin "P3") (pinfunction "3_P3") (pintype "bidirectional"))
    )
    (net (code "113") (name "unconnected-(J9-4-PadP4)") (class "Default")
      (node (ref "J9") (pin "P4") (pinfunction "4_P4") (pintype "bidirectional"))
    )
    (net (code "114") (name "unconnected-(J10-LVP-PadP6)") (class "Default")
      (node (ref "J10") (pin "P6") (pinfunction "LVP_P6") (pintype "bidirectional"))
    )
    (net (code "115") (name "unconnected-(U$1-PadSHIELD1)") (class "Default")
      (node (ref "U$1") (pin "SHIELD1") (pinfunction "SHIELD1_SHIELD1") (pintype "bidirectional"))
    )
    (net (code "116") (name "unconnected-(U$1-PadSHIELD2)") (class "Default")
      (node (ref "U$1") (pin "SHIELD2") (pinfunction "SHIELD2_SHIELD2") (pintype "bidirectional"))
    )
    (net (code "117") (name "unconnected-(U1-RP24{slash}PMA5{slash}CN20{slash}RC8-Pad4)") (class "Default")
      (node (ref "U1") (pin "4") (pinfunction "RP24/PMA5/CN20/RC8_4") (pintype "bidirectional"))
    )
    (net (code "118") (name "unconnected-(U4-ATEST1-PadP$46)") (class "Default")
      (node (ref "U4") (pin "P$46") (pinfunction "ATEST1_P$46") (pintype "bidirectional"))
    )
    (net (code "119") (name "unconnected-(U4-ATEST2-PadP$47)") (class "Default")
      (node (ref "U4") (pin "P$47") (pinfunction "ATEST2_P$47") (pintype "bidirectional"))
    )
    (net (code "120") (name "unconnected-(U4-FLASH_CS-PadP$36)") (class "Default")
      (node (ref "U4") (pin "P$36") (pinfunction "FLASH_CS_P$36") (pintype "bidirectional"))
    )
    (net (code "121") (name "unconnected-(U4-I2C0{slash}~{SPI0}-PadP$53)") (class "Default")
      (node (ref "U4") (pin "P$53") (pinfunction "I2C0/~{SPI0}_P$53") (pintype "bidirectional"))
    )
    (net (code "122") (name "unconnected-(U4-MISO0-PadP$57)") (class "Default")
      (node (ref "U4") (pin "P$57") (pinfunction "MISO0_P$57") (pintype "bidirectional"))
    )
    (net (code "123") (name "unconnected-(U4-MOSI0{slash}SDA-PadP$56)") (class "Default")
      (node (ref "U4") (pin "P$56") (pinfunction "MOSI0/SDA_P$56") (pintype "bidirectional"))
    )
    (net (code "124") (name "unconnected-(U4-ONEWIRE-PadP$54)") (class "Default")
      (node (ref "U4") (pin "P$54") (pinfunction "ONEWIRE_P$54") (pintype "bidirectional"))
    )
    (net (code "125") (name "unconnected-(U4-P2.1-PadP$39)") (class "Default")
      (node (ref "U4") (pin "P$39") (pinfunction "P2.1_P$39") (pintype "bidirectional"))
    )
    (net (code "126") (name "unconnected-(U4-P2.3-PadP$40)") (class "Default")
      (node (ref "U4") (pin "P$40") (pinfunction "P2.3_P$40") (pintype "bidirectional"))
    )
    (net (code "127") (name "unconnected-(U4-P2.6-PadP$41)") (class "Default")
      (node (ref "U4") (pin "P$41") (pinfunction "P2.6_P$41") (pintype "bidirectional"))
    )
    (net (code "128") (name "unconnected-(U4-P5.0-PadP$2)") (class "Default")
      (node (ref "U4") (pin "P$2") (pinfunction "P5.0_P$2") (pintype "bidirectional"))
    )
    (net (code "129") (name "unconnected-(U4-P5.1-PadP$3)") (class "Default")
      (node (ref "U4") (pin "P$3") (pinfunction "P5.1_P$3") (pintype "bidirectional"))
    )
    (net (code "130") (name "unconnected-(U4-P5.2-PadP$4)") (class "Default")
      (node (ref "U4") (pin "P$4") (pinfunction "P5.2_P$4") (pintype "bidirectional"))
    )
    (net (code "131") (name "unconnected-(U4-P5.7-PadP$9)") (class "Default")
      (node (ref "U4") (pin "P$9") (pinfunction "P5.7_P$9") (pintype "bidirectional"))
    )
    (net (code "132") (name "unconnected-(U4-RADIO_CCA-PadP$49)") (class "Default")
      (node (ref "U4") (pin "P$49") (pinfunction "RADIO_CCA_P$49") (pintype "bidirectional"))
    )
    (net (code "133") (name "unconnected-(U4-RADIO_CS-PadP$48)") (class "Default")
      (node (ref "U4") (pin "P$48") (pinfunction "RADIO_CS_P$48") (pintype "bidirectional"))
    )
    (net (code "134") (name "unconnected-(U4-RADIO_SFD-PadP$50)") (class "Default")
      (node (ref "U4") (pin "P$50") (pinfunction "RADIO_SFD_P$50") (pintype "bidirectional"))
    )
    (net (code "135") (name "unconnected-(U4-RFTXRX-PadP$45)") (class "Default")
      (node (ref "U4") (pin "P$45") (pinfunction "RFTXRX_P$45") (pintype "bidirectional"))
    )
    (net (code "136") (name "unconnected-(U4-SCLK0{slash}SCL-PadP$58)") (class "Default")
      (node (ref "U4") (pin "P$58") (pinfunction "SCLK0/SCL_P$58") (pintype "bidirectional"))
    )
    (net (code "137") (name "unconnected-(U4-STE0-PadP$55)") (class "Default")
      (node (ref "U4") (pin "P$55") (pinfunction "STE0_P$55") (pintype "bidirectional"))
    )
    (net (code "138") (name "unconnected-(U4-UART0RX-PadP$60)") (class "Default")
      (node (ref "U4") (pin "P$60") (pinfunction "UART0RX_P$60") (pintype "bidirectional"))
    )
    (net (code "139") (name "unconnected-(U4-UART0TX-PadP$59)") (class "Default")
      (node (ref "U4") (pin "P$59") (pinfunction "UART0TX_P$59") (pintype "bidirectional"))
    )
    (net (code "140") (name "unconnected-(U4-VEREF+-PadP$28)") (class "Default")
      (node (ref "U4") (pin "P$28") (pinfunction "VEREF+_P$28") (pintype "bidirectional"))
    )
    (net (code "141") (name "unconnected-(U4-VEREF--PadP$29)") (class "Default")
      (node (ref "U4") (pin "P$29") (pinfunction "VEREF-_P$29") (pintype "bidirectional"))
    )
    (net (code "142") (name "unconnected-(U4-VREF+-PadP$27)") (class "Default")
      (node (ref "U4") (pin "P$27") (pinfunction "VREF+_P$27") (pintype "bidirectional"))
    )
    (net (code "143") (name "unconnected-(U4-XOSC16IN-PadP$64)") (class "Default")
      (node (ref "U4") (pin "P$64") (pinfunction "XOSC16IN_P$64") (pintype "bidirectional"))
    )
    (net (code "144") (name "unconnected-(U4-XOSC16OUT-PadP$63)") (class "Default")
      (node (ref "U4") (pin "P$63") (pinfunction "XOSC16OUT_P$63") (pintype "bidirectional"))
    )
    (net (code "145") (name "unconnected-(U4-XT2IN-PadP$11)") (class "Default")
      (node (ref "U4") (pin "P$11") (pinfunction "XT2IN_P$11") (pintype "bidirectional"))
    )
    (net (code "146") (name "unconnected-(U4-XT2OUT-PadP$10)") (class "Default")
      (node (ref "U4") (pin "P$10") (pinfunction "XT2OUT_P$10") (pintype "bidirectional"))
    )
  )
)
